# nanoController.net
KiCad netlist of a schematic drawn in EAGLE
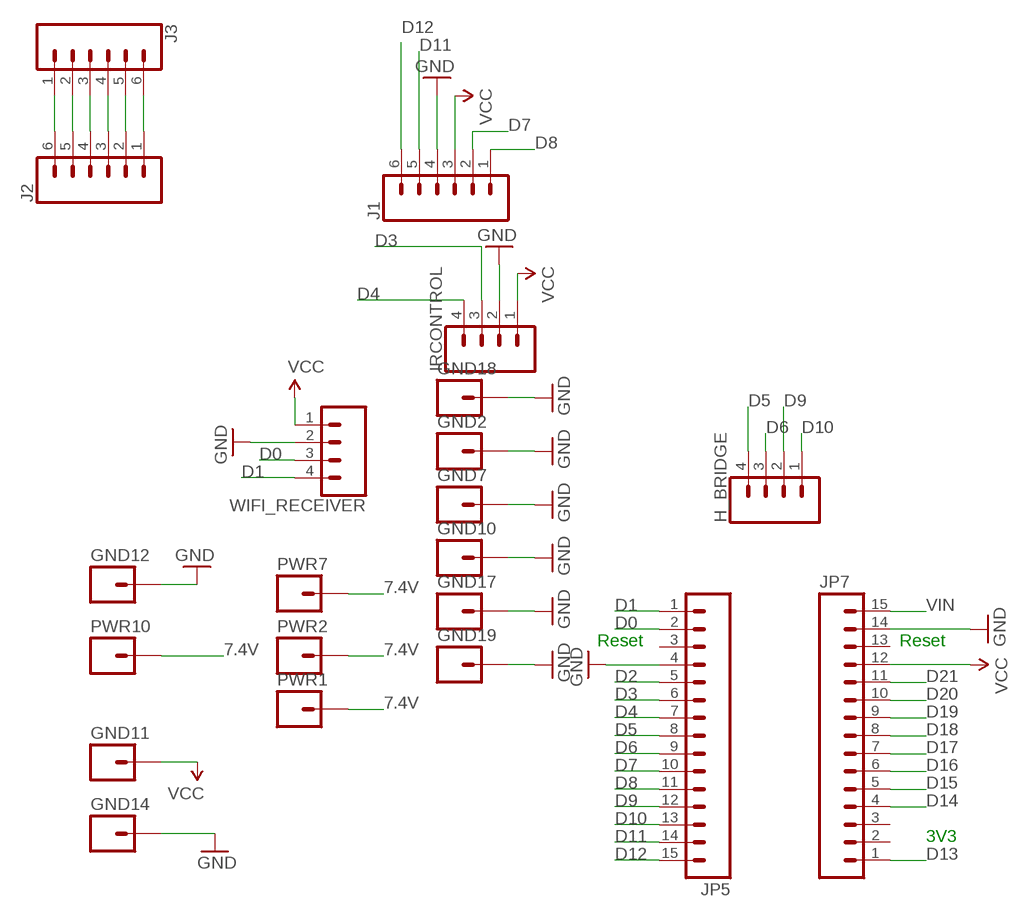
[diagram p0: schematic, sheet 1]

(export (version "E")
  (design (tool "Eeschema 10.0.6"))
  (components
    (comp (ref "GND2")
      (value "M01PTH_LONGPAD")
      (footprint "eagle-import:1X01_LONGPAD")
      (libsource (lib "eagle-import") (part "M01PTH_LONGPAD"))
    )
    (comp (ref "GND7")
      (value "M01PTH_LONGPAD")
      (footprint "eagle-import:1X01_LONGPAD")
      (libsource (lib "eagle-import") (part "M01PTH_LONGPAD"))
    )
    (comp (ref "GND10")
      (value "M01PTH_LONGPAD")
      (footprint "eagle-import:1X01_LONGPAD")
      (libsource (lib "eagle-import") (part "M01PTH_LONGPAD"))
    )
    (comp (ref "GND11")
      (value "M01PTH_LONGPAD")
      (footprint "eagle-import:1X01_LONGPAD")
      (libsource (lib "eagle-import") (part "M01PTH_LONGPAD"))
    )
    (comp (ref "GND12")
      (value "M01PTH_LONGPAD")
      (footprint "eagle-import:1X01_LONGPAD")
      (libsource (lib "eagle-import") (part "M01PTH_LONGPAD"))
    )
    (comp (ref "GND14")
      (value "M01PTH_LONGPAD")
      (footprint "eagle-import:1X01_LONGPAD")
      (libsource (lib "eagle-import") (part "M01PTH_LONGPAD"))
    )
    (comp (ref "GND17")
      (value "M01PTH_LONGPAD")
      (footprint "eagle-import:1X01_LONGPAD")
      (libsource (lib "eagle-import") (part "M01PTH_LONGPAD"))
    )
    (comp (ref "GND18")
      (value "M01PTH_LONGPAD")
      (footprint "eagle-import:1X01_LONGPAD")
      (libsource (lib "eagle-import") (part "M01PTH_LONGPAD"))
    )
    (comp (ref "GND19")
      (value "M01PTH_LONGPAD")
      (footprint "eagle-import:1X01_LONGPAD")
      (libsource (lib "eagle-import") (part "M01PTH_LONGPAD"))
    )
    (comp (ref "H_BRIDGE")
      (value "CONN_04LONGPADS")
      (footprint "eagle-import:1X04_LONGPADS")
      (libsource (lib "eagle-import") (part "CONN_04LONGPADS"))
    )
    (comp (ref "IRCONTROL")
      (value "CONN_04LONGPADS")
      (footprint "eagle-import:1X04_LONGPADS")
      (libsource (lib "eagle-import") (part "CONN_04LONGPADS"))
    )
    (comp (ref "J1")
      (value "CONN_06SILK_FEMALE_PTH")
      (footprint "eagle-import:1X06")
      (libsource (lib "eagle-import") (part "CONN_06SILK_FEMALE_PTH"))
    )
    (comp (ref "J2")
      (value "CONN_06SILK_FEMALE_PTH")
      (footprint "eagle-import:1X06")
      (libsource (lib "eagle-import") (part "CONN_06SILK_FEMALE_PTH"))
    )
    (comp (ref "J3")
      (value "CONN_06SILK_FEMALE_PTH")
      (footprint "eagle-import:1X06")
      (libsource (lib "eagle-import") (part "CONN_06SILK_FEMALE_PTH"))
    )
    (comp (ref "JP5")
      (value "M15")
      (footprint "eagle-import:1X15")
      (libsource (lib "eagle-import") (part "M15"))
    )
    (comp (ref "JP7")
      (value "M15")
      (footprint "eagle-import:1X15")
      (libsource (lib "eagle-import") (part "M15"))
    )
    (comp (ref "PWR1")
      (value "M01PTH_LONGPAD")
      (footprint "eagle-import:1X01_LONGPAD")
      (libsource (lib "eagle-import") (part "M01PTH_LONGPAD"))
    )
    (comp (ref "PWR2")
      (value "M01PTH_LONGPAD")
      (footprint "eagle-import:1X01_LONGPAD")
      (libsource (lib "eagle-import") (part "M01PTH_LONGPAD"))
    )
    (comp (ref "PWR7")
      (value "M01PTH_LONGPAD")
      (footprint "eagle-import:1X01_LONGPAD")
      (libsource (lib "eagle-import") (part "M01PTH_LONGPAD"))
    )
    (comp (ref "PWR10")
      (value "M01PTH_LONGPAD")
      (footprint "eagle-import:1X01_LONGPAD")
      (libsource (lib "eagle-import") (part "M01PTH_LONGPAD"))
    )
    (comp (ref "WIFI_RECEIVER")
      (value "CONN_04LONGPADS")
      (footprint "eagle-import:1X04_LONGPADS")
      (libsource (lib "eagle-import") (part "CONN_04LONGPADS"))
    )
  )
  (nets
    (net (code "1") (name "/7.4V") (class "Default")
      (node (ref "PWR1") (pin "1") (pinfunction "1_1") (pintype "passive"))
      (node (ref "PWR10") (pin "1") (pinfunction "1_1") (pintype "passive"))
      (node (ref "PWR2") (pin "1") (pinfunction "1_1") (pintype "passive"))
      (node (ref "PWR7") (pin "1") (pinfunction "1_1") (pintype "passive"))
    )
    (net (code "2") (name "/D0") (class "Default")
      (node (ref "JP5") (pin "2") (pinfunction "2_2") (pintype "passive"))
      (node (ref "WIFI_RECEIVER") (pin "3") (pinfunction "3_3") (pintype "passive"))
    )
    (net (code "3") (name "/D1") (class "Default")
      (node (ref "JP5") (pin "1") (pinfunction "1_1") (pintype "passive"))
      (node (ref "WIFI_RECEIVER") (pin "4") (pinfunction "4_4") (pintype "passive"))
    )
    (net (code "4") (name "/D2") (class "Default")
      (node (ref "JP5") (pin "5") (pinfunction "5_5") (pintype "passive"))
    )
    (net (code "5") (name "/D3") (class "Default")
      (node (ref "IRCONTROL") (pin "3") (pinfunction "3_3") (pintype "passive"))
      (node (ref "JP5") (pin "6") (pinfunction "6_6") (pintype "passive"))
    )
    (net (code "6") (name "/D4") (class "Default")
      (node (ref "IRCONTROL") (pin "4") (pinfunction "4_4") (pintype "passive"))
      (node (ref "JP5") (pin "7") (pinfunction "7_7") (pintype "passive"))
    )
    (net (code "7") (name "/D5") (class "Default")
      (node (ref "H_BRIDGE") (pin "4") (pinfunction "4_4") (pintype "passive"))
      (node (ref "JP5") (pin "8") (pinfunction "8_8") (pintype "passive"))
    )
    (net (code "8") (name "/D6") (class "Default")
      (node (ref "H_BRIDGE") (pin "3") (pinfunction "3_3") (pintype "passive"))
      (node (ref "JP5") (pin "9") (pinfunction "9_9") (pintype "passive"))
    )
    (net (code "9") (name "/D7") (class "Default")
      (node (ref "J1") (pin "2") (pinfunction "2_2") (pintype "passive"))
      (node (ref "JP5") (pin "10") (pinfunction "10_10") (pintype "passive"))
    )
    (net (code "10") (name "/D8") (class "Default")
      (node (ref "J1") (pin "1") (pinfunction "1_1") (pintype "passive"))
      (node (ref "JP5") (pin "11") (pinfunction "11_11") (pintype "passive"))
    )
    (net (code "11") (name "/D9") (class "Default")
      (node (ref "H_BRIDGE") (pin "2") (pinfunction "2_2") (pintype "passive"))
      (node (ref "JP5") (pin "12") (pinfunction "12_12") (pintype "passive"))
    )
    (net (code "12") (name "/D10") (class "Default")
      (node (ref "H_BRIDGE") (pin "1") (pinfunction "1_1") (pintype "passive"))
      (node (ref "JP5") (pin "13") (pinfunction "13_13") (pintype "passive"))
    )
    (net (code "13") (name "/D11") (class "Default")
      (node (ref "J1") (pin "5") (pinfunction "5_5") (pintype "passive"))
      (node (ref "JP5") (pin "14") (pinfunction "14_14") (pintype "passive"))
    )
    (net (code "14") (name "/D12") (class "Default")
      (node (ref "J1") (pin "6") (pinfunction "6_6") (pintype "passive"))
      (node (ref "JP5") (pin "15") (pinfunction "15_15") (pintype "passive"))
    )
    (net (code "15") (name "/D13") (class "Default")
      (node (ref "JP7") (pin "1") (pinfunction "1_1") (pintype "passive"))
    )
    (net (code "16") (name "/D14") (class "Default")
      (node (ref "JP7") (pin "4") (pinfunction "4_4") (pintype "passive"))
    )
    (net (code "17") (name "/D15") (class "Default")
      (node (ref "JP7") (pin "5") (pinfunction "5_5") (pintype "passive"))
    )
    (net (code "18") (name "/D16") (class "Default")
      (node (ref "JP7") (pin "6") (pinfunction "6_6") (pintype "passive"))
    )
    (net (code "19") (name "/D17") (class "Default")
      (node (ref "JP7") (pin "7") (pinfunction "7_7") (pintype "passive"))
    )
    (net (code "20") (name "/D18") (class "Default")
      (node (ref "JP7") (pin "8") (pinfunction "8_8") (pintype "passive"))
    )
    (net (code "21") (name "/D19") (class "Default")
      (node (ref "JP7") (pin "9") (pinfunction "9_9") (pintype "passive"))
    )
    (net (code "22") (name "/D20") (class "Default")
      (node (ref "JP7") (pin "10") (pinfunction "10_10") (pintype "passive"))
    )
    (net (code "23") (name "/D21") (class "Default")
      (node (ref "JP7") (pin "11") (pinfunction "11_11") (pintype "passive"))
    )
    (net (code "24") (name "/VIN") (class "Default")
      (node (ref "JP7") (pin "15") (pinfunction "15_15") (pintype "passive"))
    )
    (net (code "25") (name "GND") (class "Default")
      (node (ref "GND10") (pin "1") (pinfunction "1_1") (pintype "passive"))
      (node (ref "GND12") (pin "1") (pinfunction "1_1") (pintype "passive"))
      (node (ref "GND14") (pin "1") (pinfunction "1_1") (pintype "passive"))
      (node (ref "GND17") (pin "1") (pinfunction "1_1") (pintype "passive"))
      (node (ref "GND18") (pin "1") (pinfunction "1_1") (pintype "passive"))
      (node (ref "GND19") (pin "1") (pinfunction "1_1") (pintype "passive"))
      (node (ref "GND2") (pin "1") (pinfunction "1_1") (pintype "passive"))
      (node (ref "GND7") (pin "1") (pinfunction "1_1") (pintype "passive"))
      (node (ref "IRCONTROL") (pin "2") (pinfunction "2_2") (pintype "passive"))
      (node (ref "J1") (pin "4") (pinfunction "4_4") (pintype "passive"))
      (node (ref "JP5") (pin "4") (pinfunction "4_4") (pintype "passive"))
      (node (ref "JP7") (pin "14") (pinfunction "14_14") (pintype "passive"))
      (node (ref "WIFI_RECEIVER") (pin "2") (pinfunction "2_2") (pintype "passive"))
    )
    (net (code "26") (name "Net-(J2-Pad1)") (class "Default")
      (node (ref "J2") (pin "1") (pinfunction "1_1") (pintype "passive"))
      (node (ref "J3") (pin "6") (pinfunction "6_6") (pintype "passive"))
    )
    (net (code "27") (name "Net-(J2-Pad2)") (class "Default")
      (node (ref "J2") (pin "2") (pinfunction "2_2") (pintype "passive"))
      (node (ref "J3") (pin "5") (pinfunction "5_5") (pintype "passive"))
    )
    (net (code "28") (name "Net-(J2-Pad3)") (class "Default")
      (node (ref "J2") (pin "3") (pinfunction "3_3") (pintype "passive"))
      (node (ref "J3") (pin "4") (pinfunction "4_4") (pintype "passive"))
    )
    (net (code "29") (name "Net-(J2-Pad4)") (class "Default")
      (node (ref "J2") (pin "4") (pinfunction "4_4") (pintype "passive"))
      (node (ref "J3") (pin "3") (pinfunction "3_3") (pintype "passive"))
    )
    (net (code "30") (name "Net-(J2-Pad5)") (class "Default")
      (node (ref "J2") (pin "5") (pinfunction "5_5") (pintype "passive"))
      (node (ref "J3") (pin "2") (pinfunction "2_2") (pintype "passive"))
    )
    (net (code "31") (name "Net-(J2-Pad6)") (class "Default")
      (node (ref "J2") (pin "6") (pinfunction "6_6") (pintype "passive"))
      (node (ref "J3") (pin "1") (pinfunction "1_1") (pintype "passive"))
    )
    (net (code "32") (name "VCC") (class "Default")
      (node (ref "GND11") (pin "1") (pinfunction "1_1") (pintype "passive"))
      (node (ref "IRCONTROL") (pin "1") (pinfunction "1_1") (pintype "passive"))
      (node (ref "J1") (pin "3") (pinfunction "3_3") (pintype "passive"))
      (node (ref "JP7") (pin "12") (pinfunction "12_12") (pintype "passive"))
      (node (ref "WIFI_RECEIVER") (pin "1") (pinfunction "1_1") (pintype "passive"))
    )
    (net (code "33") (name "unconnected-(JP5-Pad3)") (class "Default")
      (node (ref "JP5") (pin "3") (pinfunction "3_3") (pintype "passive"))
    )
    (net (code "34") (name "unconnected-(JP7-Pad2)") (class "Default")
      (node (ref "JP7") (pin "2") (pinfunction "2_2") (pintype "passive"))
    )
    (net (code "35") (name "unconnected-(JP7-Pad3)") (class "Default")
      (node (ref "JP7") (pin "3") (pinfunction "3_3") (pintype "passive"))
    )
    (net (code "36") (name "unconnected-(JP7-Pad13)") (class "Default")
      (node (ref "JP7") (pin "13") (pinfunction "13_13") (pintype "passive"))
    )
  )
)
